# camera.net
KiCad netlist of a schematic drawn in Altium Designer
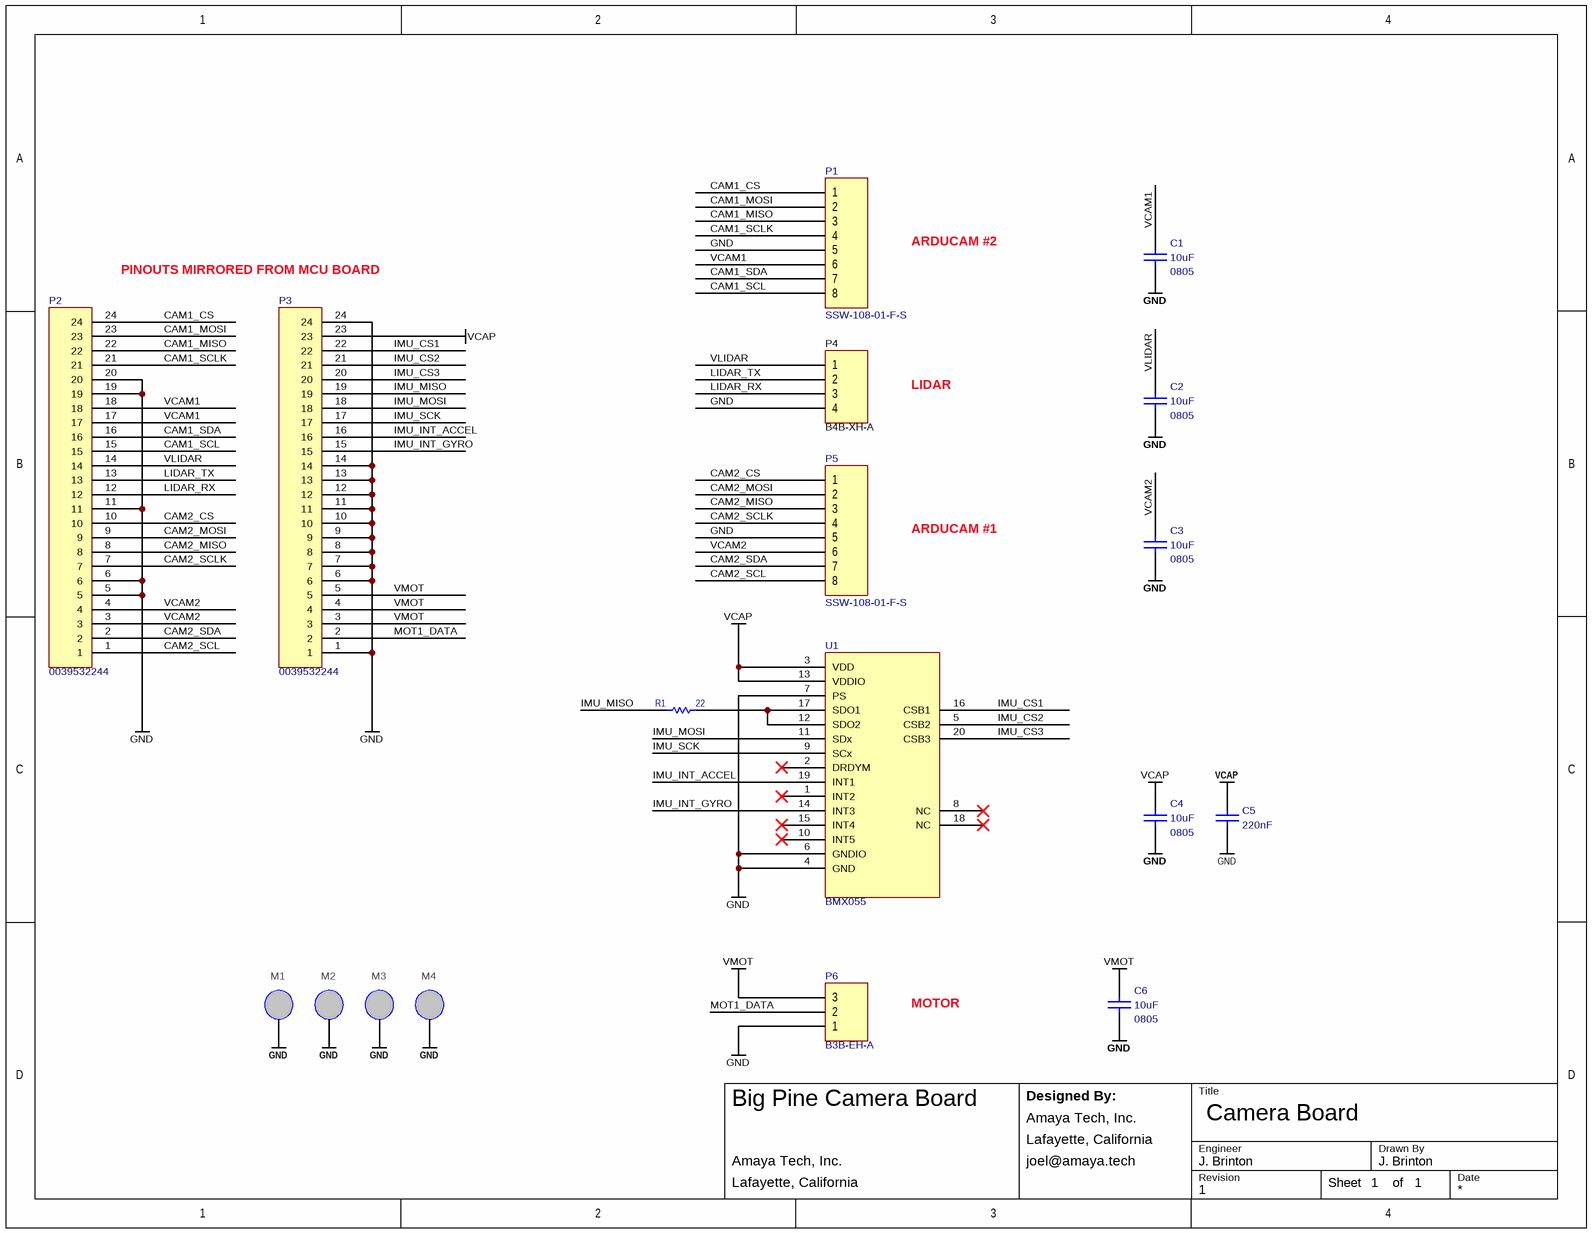
[diagram p0: camera.SchDoc]

(export (version "E")
  (design (tool "Eeschema 10.0.6"))
  (components
    (comp (ref "C1")
      (value "10uF")
      (footprint "CAPC200X125X145L45N")
      (description "Ceramic Capacitor 10uF ±10% 16V X7R 0805")
      (fields
        (field (name "MANUFACTURER") "Samsung")
        (field (name "TOLERANCE") "±10%")
        (field (name "PACKAGE") "0805")
      )
      (libsource (lib "capacitors") (part "CAP"))
    )
    (comp (ref "C2")
      (value "10uF")
      (footprint "CAPC200X125X145L45N")
      (description "Ceramic Capacitor 10uF ±10% 16V X7R 0805")
      (fields
        (field (name "MANUFACTURER") "Samsung")
        (field (name "TOLERANCE") "±10%")
        (field (name "PACKAGE") "0805")
      )
      (libsource (lib "capacitors") (part "CAP"))
    )
    (comp (ref "C3")
      (value "10uF")
      (footprint "CAPC200X125X145L45N")
      (description "Ceramic Capacitor 10uF ±10% 16V X7R 0805")
      (fields
        (field (name "MANUFACTURER") "Samsung")
        (field (name "TOLERANCE") "±10%")
        (field (name "PACKAGE") "0805")
      )
      (libsource (lib "capacitors") (part "CAP"))
    )
    (comp (ref "C4")
      (value "10uF")
      (footprint "CAPC200X125X145L45N")
      (description "Ceramic Capacitor 10uF ±10% 16V X7R 0805")
      (fields
        (field (name "MANUFACTURER") "Samsung")
        (field (name "TOLERANCE") "±10%")
        (field (name "PACKAGE") "0805")
      )
      (libsource (lib "capacitors") (part "CAP"))
    )
    (comp (ref "C5")
      (value "220nF")
      (footprint "CAPC100X50X55L25N")
      (description "Ceramic Capacitor 220nF ±10% 25V X7R 0402")
      (fields (field (name "MANUFACTURER") "TDK") (field (name "TOLERANCE") "±10%"))
      (libsource (lib "capacitors") (part "CAP"))
    )
    (comp (ref "C6")
      (value "10uF")
      (footprint "CAPC200X125X145L45N")
      (description "Ceramic Capacitor 10uF ±10% 16V X7R 0805")
      (fields
        (field (name "MANUFACTURER") "Samsung")
        (field (name "TOLERANCE") "±10%")
        (field (name "PACKAGE") "0805")
      )
      (libsource (lib "capacitors") (part "CAP"))
    )
    (comp (ref "M1") (value "MOUNT") (footprint "M4_MOUNT") (libsource (lib "generic") (part "MOUNT")))
    (comp (ref "M2") (value "MOUNT") (footprint "M4_MOUNT") (libsource (lib "generic") (part "MOUNT")))
    (comp (ref "M3") (value "MOUNT") (footprint "M4_MOUNT") (libsource (lib "generic") (part "MOUNT")))
    (comp (ref "M4") (value "MOUNT") (footprint "M4_MOUNT") (libsource (lib "generic") (part "MOUNT")))
    (comp (ref "P1")
      (value "SSW-108-01-F-S")
      (footprint "samtec:SSW-108-01-F-S")
      (description "Through-hole post socket 0.1\" pitch")
      (fields (field (name "MANUFACTURER") "Samtec"))
      (libsource (lib "Miscellaneous Connectors") (part "Header 8"))
    )
    (comp (ref "P2")
      (value "0039532244")
      (footprint "0039532244")
      (description "FPC connector")
      (fields (field (name "MANUFACTURER") "Molex"))
      (libsource (lib "molex") (part "0039532244"))
    )
    (comp (ref "P3")
      (value "0039532244")
      (footprint "0039532244")
      (description "FPC connector")
      (fields (field (name "MANUFACTURER") "Molex"))
      (libsource (lib "molex") (part "0039532244"))
    )
    (comp (ref "P4")
      (value "B4B-XH-A")
      (footprint "HDR1X4")
      (description "Header, 4-Pin")
      (fields (field (name "MANUFACTURER") "JST"))
      (libsource (lib "Miscellaneous Connectors") (part "Header 4"))
    )
    (comp (ref "P5")
      (value "SSW-108-01-F-S")
      (footprint "samtec:SSW-108-01-F-S")
      (description "Through-hole post socket 0.1\" pitch")
      (fields (field (name "MANUFACTURER") "Samtec"))
      (libsource (lib "Miscellaneous Connectors") (part "Header 8"))
    )
    (comp (ref "P6")
      (value "B3B-EH-A")
      (footprint "B3B-EH-A")
      (description "2.5mm pitch crimp connector")
      (fields (field (name "MANUFACTURER") "JST"))
      (libsource (lib "Miscellaneous Connectors") (part "Header 3"))
    )
    (comp (ref "R1")
      (value "22")
      (footprint "RESC2012X70N")
      (description "Thick Film Resistor 22 ±1% 0805")
      (fields (field (name "MANUFACTURER") "Panasonic") (field (name "TOLERANCE") "±1%"))
      (libsource (lib "Graviton") (part "RES 0402"))
    )
    (comp (ref "U1")
      (value "BMX055")
      (footprint "bosch:BMX055")
      (description "9-DOF Sensor Module")
      (fields (field (name "MANUFACTURER") "Bosch") (field (name "MANUFACTURER P/N") "BMX055"))
      (libsource (lib "bosch") (part "BMX055"))
    )
  )
  (nets
    (net (code "1") (name "/CAM1_CS") (class "Default")
      (node (ref "P1") (pin "1") (pinfunction "1_1") (pintype "passive"))
      (node (ref "P2") (pin "24") (pinfunction "24_24") (pintype "passive"))
    )
    (net (code "2") (name "/CAM1_MISO") (class "Default")
      (node (ref "P1") (pin "3") (pinfunction "3_3") (pintype "passive"))
      (node (ref "P2") (pin "22") (pinfunction "22_22") (pintype "passive"))
    )
    (net (code "3") (name "/CAM1_MOSI") (class "Default")
      (node (ref "P1") (pin "2") (pinfunction "2_2") (pintype "passive"))
      (node (ref "P2") (pin "23") (pinfunction "23_23") (pintype "passive"))
    )
    (net (code "4") (name "/CAM1_SCL") (class "Default")
      (node (ref "P1") (pin "8") (pinfunction "8_8") (pintype "passive"))
      (node (ref "P2") (pin "15") (pinfunction "15_15") (pintype "passive"))
    )
    (net (code "5") (name "/CAM1_SCLK") (class "Default")
      (node (ref "P1") (pin "4") (pinfunction "4_4") (pintype "passive"))
      (node (ref "P2") (pin "21") (pinfunction "21_21") (pintype "passive"))
    )
    (net (code "6") (name "/CAM1_SDA") (class "Default")
      (node (ref "P1") (pin "7") (pinfunction "7_7") (pintype "passive"))
      (node (ref "P2") (pin "16") (pinfunction "16_16") (pintype "passive"))
    )
    (net (code "7") (name "/CAM2_CS") (class "Default")
      (node (ref "P2") (pin "10") (pinfunction "10_10") (pintype "passive"))
      (node (ref "P5") (pin "1") (pinfunction "1_1") (pintype "passive"))
    )
    (net (code "8") (name "/CAM2_MISO") (class "Default")
      (node (ref "P2") (pin "8") (pinfunction "8_8") (pintype "passive"))
      (node (ref "P5") (pin "3") (pinfunction "3_3") (pintype "passive"))
    )
    (net (code "9") (name "/CAM2_MOSI") (class "Default")
      (node (ref "P2") (pin "9") (pinfunction "9_9") (pintype "passive"))
      (node (ref "P5") (pin "2") (pinfunction "2_2") (pintype "passive"))
    )
    (net (code "10") (name "/CAM2_SCL") (class "Default")
      (node (ref "P2") (pin "1") (pinfunction "1_1") (pintype "passive"))
      (node (ref "P5") (pin "8") (pinfunction "8_8") (pintype "passive"))
    )
    (net (code "11") (name "/CAM2_SCLK") (class "Default")
      (node (ref "P2") (pin "7") (pinfunction "7_7") (pintype "passive"))
      (node (ref "P5") (pin "4") (pinfunction "4_4") (pintype "passive"))
    )
    (net (code "12") (name "/CAM2_SDA") (class "Default")
      (node (ref "P2") (pin "2") (pinfunction "2_2") (pintype "passive"))
      (node (ref "P5") (pin "7") (pinfunction "7_7") (pintype "passive"))
    )
    (net (code "13") (name "/IMU_CS1") (class "Default")
      (node (ref "P3") (pin "22") (pinfunction "22_22") (pintype "passive"))
      (node (ref "U1") (pin "16") (pinfunction "CSB1_16") (pintype "passive"))
    )
    (net (code "14") (name "/IMU_CS2") (class "Default")
      (node (ref "P3") (pin "21") (pinfunction "21_21") (pintype "passive"))
      (node (ref "U1") (pin "5") (pinfunction "CSB2_5") (pintype "passive"))
    )
    (net (code "15") (name "/IMU_CS3") (class "Default")
      (node (ref "P3") (pin "20") (pinfunction "20_20") (pintype "passive"))
      (node (ref "U1") (pin "20") (pinfunction "CSB3_20") (pintype "passive"))
    )
    (net (code "16") (name "/IMU_INT_ACCEL") (class "Default")
      (node (ref "P3") (pin "16") (pinfunction "16_16") (pintype "passive"))
      (node (ref "U1") (pin "19") (pinfunction "INT1_19") (pintype "passive"))
    )
    (net (code "17") (name "/IMU_INT_GYRO") (class "Default")
      (node (ref "P3") (pin "15") (pinfunction "15_15") (pintype "passive"))
      (node (ref "U1") (pin "14") (pinfunction "INT3_14") (pintype "passive"))
    )
    (net (code "18") (name "/IMU_MISO") (class "Default")
      (node (ref "P3") (pin "19") (pinfunction "19_19") (pintype "passive"))
      (node (ref "R1") (pin "2") (pinfunction "2_2") (pintype "passive"))
    )
    (net (code "19") (name "/IMU_MOSI") (class "Default")
      (node (ref "P3") (pin "18") (pinfunction "18_18") (pintype "passive"))
      (node (ref "U1") (pin "11") (pinfunction "SDx_11") (pintype "passive"))
    )
    (net (code "20") (name "/IMU_SCK") (class "Default")
      (node (ref "P3") (pin "17") (pinfunction "17_17") (pintype "passive"))
      (node (ref "U1") (pin "9") (pinfunction "SCx_9") (pintype "passive"))
    )
    (net (code "21") (name "/LIDAR_RX") (class "Default")
      (node (ref "P2") (pin "12") (pinfunction "12_12") (pintype "passive"))
      (node (ref "P4") (pin "3") (pinfunction "3_3") (pintype "passive"))
    )
    (net (code "22") (name "/LIDAR_TX") (class "Default")
      (node (ref "P2") (pin "13") (pinfunction "13_13") (pintype "passive"))
      (node (ref "P4") (pin "2") (pinfunction "2_2") (pintype "passive"))
    )
    (net (code "23") (name "/MOT1_DATA") (class "Default")
      (node (ref "P3") (pin "2") (pinfunction "2_2") (pintype "passive"))
      (node (ref "P6") (pin "2") (pinfunction "2_2") (pintype "passive"))
    )
    (net (code "24") (name "/VCAM1") (class "Default")
      (node (ref "C1") (pin "1") (pinfunction "1_1") (pintype "passive"))
      (node (ref "P1") (pin "6") (pinfunction "6_6") (pintype "passive"))
      (node (ref "P2") (pin "17") (pinfunction "17_17") (pintype "passive"))
      (node (ref "P2") (pin "18") (pinfunction "18_18") (pintype "passive"))
    )
    (net (code "25") (name "/VCAM2") (class "Default")
      (node (ref "C3") (pin "1") (pinfunction "1_1") (pintype "passive"))
      (node (ref "P2") (pin "3") (pinfunction "3_3") (pintype "passive"))
      (node (ref "P2") (pin "4") (pinfunction "4_4") (pintype "passive"))
      (node (ref "P5") (pin "6") (pinfunction "6_6") (pintype "passive"))
    )
    (net (code "26") (name "/VLIDAR") (class "Default")
      (node (ref "C2") (pin "1") (pinfunction "1_1") (pintype "passive"))
      (node (ref "P2") (pin "14") (pinfunction "14_14") (pintype "passive"))
      (node (ref "P4") (pin "1") (pinfunction "1_1") (pintype "passive"))
    )
    (net (code "27") (name "GND") (class "Default")
      (node (ref "C1") (pin "2") (pinfunction "2_2") (pintype "passive"))
      (node (ref "C2") (pin "2") (pinfunction "2_2") (pintype "passive"))
      (node (ref "C3") (pin "2") (pinfunction "2_2") (pintype "passive"))
      (node (ref "C4") (pin "2") (pinfunction "2_2") (pintype "passive"))
      (node (ref "C5") (pin "2") (pinfunction "2_2") (pintype "passive"))
      (node (ref "C6") (pin "2") (pinfunction "2_2") (pintype "passive"))
      (node (ref "M1") (pin "1") (pinfunction "MNT_1") (pintype "passive"))
      (node (ref "M2") (pin "1") (pinfunction "MNT_1") (pintype "passive"))
      (node (ref "M3") (pin "1") (pinfunction "MNT_1") (pintype "passive"))
      (node (ref "M4") (pin "1") (pinfunction "MNT_1") (pintype "passive"))
      (node (ref "P1") (pin "5") (pinfunction "5_5") (pintype "passive"))
      (node (ref "P2") (pin "11") (pinfunction "11_11") (pintype "passive"))
      (node (ref "P2") (pin "19") (pinfunction "19_19") (pintype "passive"))
      (node (ref "P2") (pin "20") (pinfunction "20_20") (pintype "passive"))
      (node (ref "P2") (pin "5") (pinfunction "5_5") (pintype "passive"))
      (node (ref "P2") (pin "6") (pinfunction "6_6") (pintype "passive"))
      (node (ref "P3") (pin "1") (pinfunction "1_1") (pintype "passive"))
      (node (ref "P3") (pin "10") (pinfunction "10_10") (pintype "passive"))
      (node (ref "P3") (pin "11") (pinfunction "11_11") (pintype "passive"))
      (node (ref "P3") (pin "12") (pinfunction "12_12") (pintype "passive"))
      (node (ref "P3") (pin "13") (pinfunction "13_13") (pintype "passive"))
      (node (ref "P3") (pin "14") (pinfunction "14_14") (pintype "passive"))
      (node (ref "P3") (pin "24") (pinfunction "24_24") (pintype "passive"))
      (node (ref "P3") (pin "6") (pinfunction "6_6") (pintype "passive"))
      (node (ref "P3") (pin "7") (pinfunction "7_7") (pintype "passive"))
      (node (ref "P3") (pin "8") (pinfunction "8_8") (pintype "passive"))
      (node (ref "P3") (pin "9") (pinfunction "9_9") (pintype "passive"))
      (node (ref "P4") (pin "4") (pinfunction "4_4") (pintype "passive"))
      (node (ref "P5") (pin "5") (pinfunction "5_5") (pintype "passive"))
      (node (ref "P6") (pin "1") (pinfunction "1_1") (pintype "passive"))
      (node (ref "U1") (pin "4") (pinfunction "GND_4") (pintype "passive"))
      (node (ref "U1") (pin "6") (pinfunction "GNDIO_6") (pintype "passive"))
      (node (ref "U1") (pin "7") (pinfunction "PS_7") (pintype "passive"))
    )
    (net (code "28") (name "Net-(U1-SDO1)") (class "Default")
      (node (ref "R1") (pin "1") (pinfunction "1_1") (pintype "passive"))
      (node (ref "U1") (pin "12") (pinfunction "SDO2_12") (pintype "passive"))
      (node (ref "U1") (pin "17") (pinfunction "SDO1_17") (pintype "passive"))
    )
    (net (code "29") (name "VCAP") (class "Default")
      (node (ref "C4") (pin "1") (pinfunction "1_1") (pintype "passive"))
      (node (ref "C5") (pin "1") (pinfunction "1_1") (pintype "passive"))
      (node (ref "P3") (pin "23") (pinfunction "23_23") (pintype "passive"))
      (node (ref "U1") (pin "13") (pinfunction "VDDIO_13") (pintype "passive"))
      (node (ref "U1") (pin "3") (pinfunction "VDD_3") (pintype "passive"))
    )
    (net (code "30") (name "VMOT") (class "Default")
      (node (ref "C6") (pin "1") (pinfunction "1_1") (pintype "passive"))
      (node (ref "P3") (pin "3") (pinfunction "3_3") (pintype "passive"))
      (node (ref "P3") (pin "4") (pinfunction "4_4") (pintype "passive"))
      (node (ref "P3") (pin "5") (pinfunction "5_5") (pintype "passive"))
      (node (ref "P6") (pin "3") (pinfunction "3_3") (pintype "passive"))
    )
    (net (code "31") (name "unconnected-(U1-DRDYM-Pad2)") (class "Default")
      (node (ref "U1") (pin "2") (pinfunction "DRDYM_2") (pintype "passive+no_connect"))
    )
    (net (code "32") (name "unconnected-(U1-INT2-Pad1)") (class "Default")
      (node (ref "U1") (pin "1") (pinfunction "INT2_1") (pintype "passive+no_connect"))
    )
    (net (code "33") (name "unconnected-(U1-INT4-Pad15)") (class "Default")
      (node (ref "U1") (pin "15") (pinfunction "INT4_15") (pintype "passive+no_connect"))
    )
    (net (code "34") (name "unconnected-(U1-INT5-Pad10)") (class "Default")
      (node (ref "U1") (pin "10") (pinfunction "INT5_10") (pintype "passive+no_connect"))
    )
    (net (code "35") (name "unconnected-(U1-NC-Pad8)") (class "Default")
      (node (ref "U1") (pin "8") (pinfunction "NC_8") (pintype "passive+no_connect"))
    )
    (net (code "36") (name "unconnected-(U1-NC-Pad18)") (class "Default")
      (node (ref "U1") (pin "18") (pinfunction "NC_18") (pintype "passive+no_connect"))
    )
  )
)
